# H-Bridge.net
KiCad netlist of a schematic drawn in Altium Designer
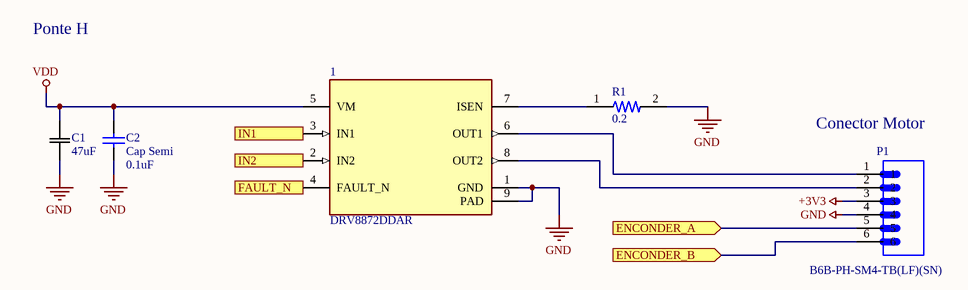
[diagram p0: H-Bridge.SchDoc]

(export (version "E")
  (design (tool "Eeschema 10.0.6"))
  (components
    (comp (ref "1")
      (value "DRV8872DDAR")
      (footprint "DDA0008H_N")
      (description "Unipolar Motor Driver NMOS PWM 8-SO PowerPad")
      (fields (field (name "MF") "Texas Instruments"))
      (libsource (lib "DRV8872DDAR") (part "DRV8872DDAR"))
    )
    (comp (ref "C1")
      (value "47uF")
      (footprint "CAP_UWF_6P3X5P00")
      (description "No Description Available")
      (fields
        (field (name "MANUFACTURER_PART_NUMBER") "UWR1E470MCL1GB")
        (field (name "COPYRIGHT") "Copyright (C) 2018 Accelerated Designs. All rights reserved")
      )
      (libsource (lib "2020-06-14_22-37-07") (part "UWR1E470MCL1GB"))
    )
    (comp (ref "C2")
      (value "Cap Semi")
      (footprint "1608[0603]")
      (description "Capacitor (Semiconductor SIM Model)")
      (fields (field (name "ALTIUM_VALUE") "0.1uF") (field (name "PUBLISHER") "Altium Limited"))
      (libsource (lib "Miscellaneous Devices") (part "Cap Semi"))
    )
    (comp (ref "P1")
      (value "B6B-PH-SM4-TB(LF)(SN)")
      (footprint "JST_B6B-PH-SM4-TB(LF)(SN)")
      (description "Connector Header Surface Mount 6 position 0.079 _2.00mm_")
      (fields (field (name "MF") "JST Sales") (field (name "MP") "B6B-PH-SM4-TB_LF__SN_"))
      (libsource (lib "B6B-PH-SM4-TB_LF__SN_") (part "B6B-PH-SM4-TB(LF)(SN)"))
    )
    (comp (ref "R1")
      (value "0.2")
      (footprint "RESC1607X60N")
      (description "1 kOhms Â±5% 0.1W, 1/10W Chip Resistor 0603 _1608 Metric_ Moisture Resistant Thick Film")
      (fields (field (name "MP") "RC0603JR-071KL") (field (name "DIGI-KEY_PART_NUMBER") "311-1.0KGRCT-ND"))
      (libsource (lib "RC0603JR-071KL") (part "RC0603JR-071KL"))
    )
  )
  (nets
    (net (code "1") (name "+3V3") (class "Default")
      (node (ref "P1") (pin "3") (pinfunction "3_3") (pintype "passive"))
    )
    (net (code "2") (name "/ENCONDER_A") (class "Default")
      (node (ref "P1") (pin "5") (pinfunction "5_5") (pintype "passive"))
    )
    (net (code "3") (name "/ENCONDER_B") (class "Default")
      (node (ref "P1") (pin "6") (pinfunction "6_6") (pintype "passive"))
    )
    (net (code "4") (name "/FAULT_N") (class "Default")
      (node (ref "1") (pin "4") (pinfunction "FAULT_N_4") (pintype "open_collector"))
    )
    (net (code "5") (name "/IN1") (class "Default")
      (node (ref "1") (pin "3") (pinfunction "IN1_3") (pintype "input"))
    )
    (net (code "6") (name "/IN2") (class "Default")
      (node (ref "1") (pin "2") (pinfunction "IN2_2") (pintype "input"))
    )
    (net (code "7") (name "GND") (class "Default")
      (node (ref "1") (pin "1") (pinfunction "GND_1") (pintype "power_in"))
      (node (ref "1") (pin "9") (pinfunction "PAD_9") (pintype "power_in"))
      (node (ref "C1") (pin "1") (pinfunction "1_1") (pintype "passive"))
      (node (ref "C2") (pin "1") (pinfunction "1_1") (pintype "passive"))
      (node (ref "P1") (pin "4") (pinfunction "4_4") (pintype "passive"))
      (node (ref "R1") (pin "2") (pinfunction "2_2") (pintype "passive"))
    )
    (net (code "8") (name "Net-(1-ISEN)") (class "Default")
      (node (ref "1") (pin "7") (pinfunction "ISEN_7") (pintype "power_in"))
      (node (ref "R1") (pin "1") (pinfunction "1_1") (pintype "passive"))
    )
    (net (code "9") (name "Net-(1-OUT1)") (class "Default")
      (node (ref "1") (pin "6") (pinfunction "OUT1_6") (pintype "output"))
      (node (ref "P1") (pin "1") (pinfunction "1_1") (pintype "passive"))
    )
    (net (code "10") (name "Net-(1-OUT2)") (class "Default")
      (node (ref "1") (pin "8") (pinfunction "OUT2_8") (pintype "output"))
      (node (ref "P1") (pin "2") (pinfunction "2_2") (pintype "passive"))
    )
    (net (code "11") (name "VDD") (class "Default")
      (node (ref "1") (pin "5") (pinfunction "VM_5") (pintype "power_in"))
      (node (ref "C1") (pin "2") (pinfunction "2_2") (pintype "passive"))
      (node (ref "C2") (pin "2") (pinfunction "2_2") (pintype "passive"))
    )
  )
)
